# USB.net
KiCad netlist of a schematic drawn in Altium Designer
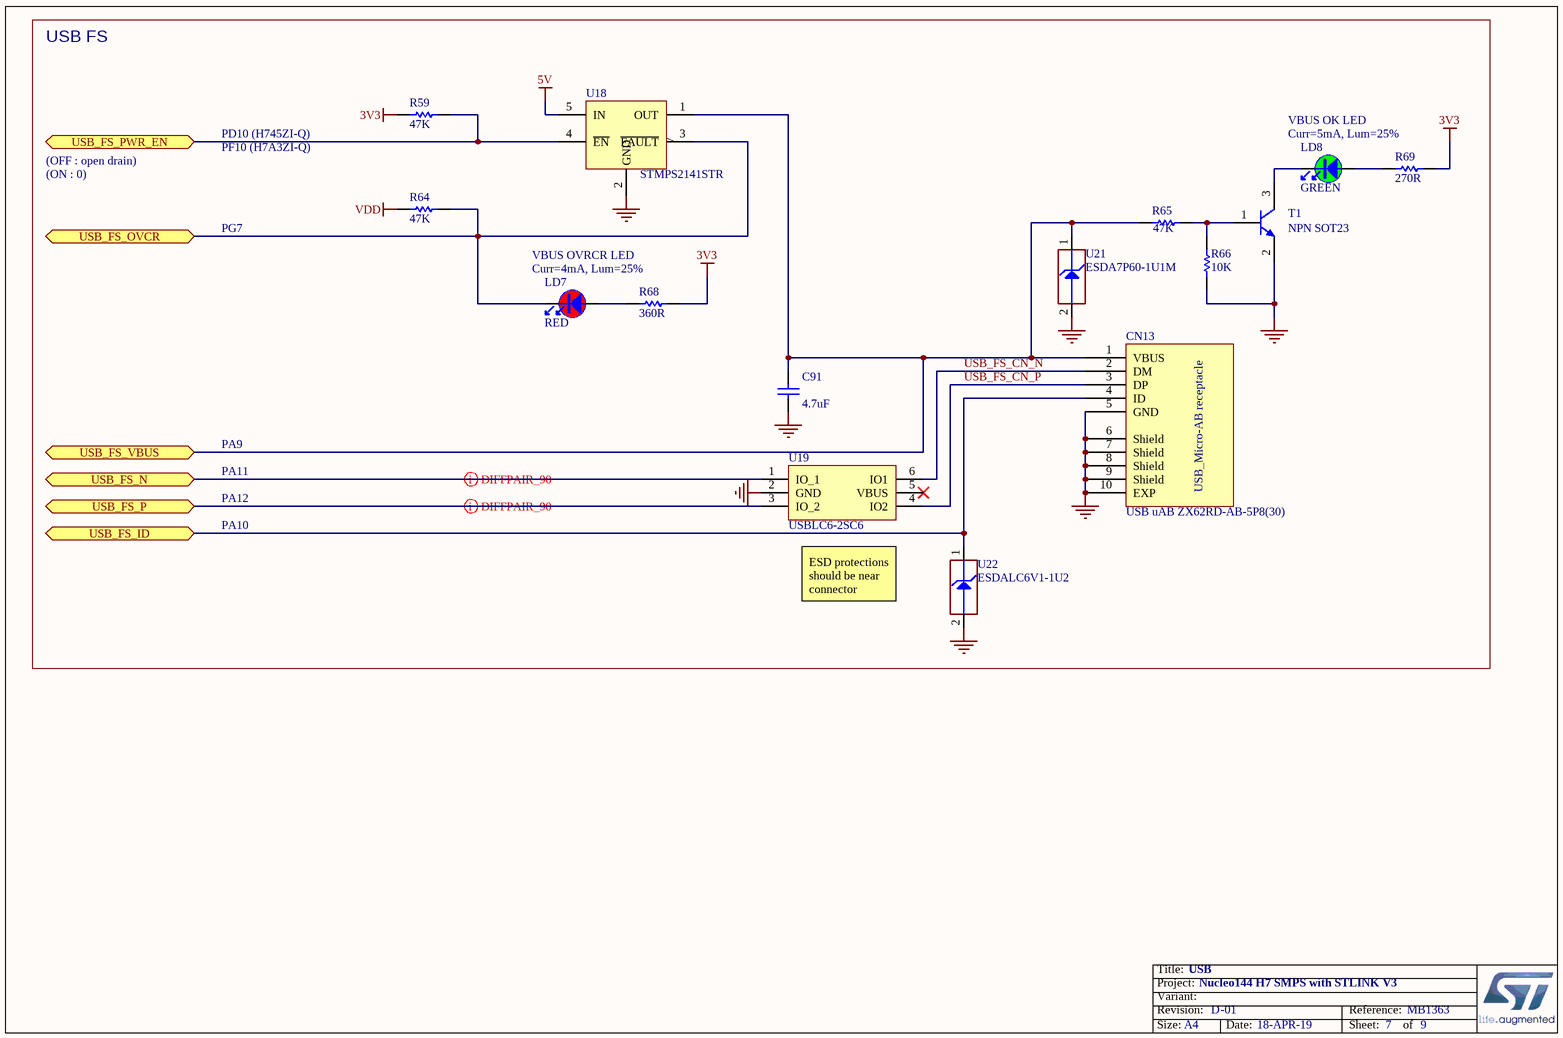
[diagram p0: USB.SchDoc]

(export (version "E")
  (design (tool "Eeschema 10.0.6"))
  (components
    (comp (ref "C91")
      (value "4.7uF")
      (footprint "C0603")
      (description "Capacitor, MLCC, 4.7uF, 16V, X5R, 10%, 0603, T=0.8mm")
      (fields
        (field (name "INTERNAL_PART_NUMBER") "MCD-00009")
        (field (name "MANUFACTURER_PART_NUMBER") "CC0603KRX5R7BB475")
        (field (name "PROVIDED_BY") "SUBCO")
      )
      (libsource (lib "MCD_PARTS_database") (part "Capacitor"))
    )
    (comp (ref "CN13")
      (value "USB uAB ZX62RD-AB-5P8(30)")
      (footprint "CON_USBMICROAB_MOLEX_47590-0001_H3")
      (fields
        (field (name "INTERNAL_PART_NUMBER") "MCD-00661")
        (field (name "MANUFACTURER_PART_NUMBER") "ZX62RD-AB-5P8(30)")
        (field (name "MANUFACTURER") "HIROSE")
        (field (name "PROVIDED_BY") "SUBCO")
      )
      (libsource (lib "MCD_PARTS_database") (part "USB_uAB_47590.0001"))
    )
    (comp (ref "LD7")
      (value "RED")
      (footprint "LED_0603_VISHAY_VLMS1300-GS08_RED_1A2K_H0P8")
      (description "LED Red, 0603 SMD, 2V Forward Voltage")
      (fields
        (field (name "INTERNAL_PART_NUMBER") "MCD-00587")
        (field (name "MANUFACTURER_PART_NUMBER") "VLMS1300-GS08")
        (field (name "PROVIDED_BY") "SUBCO")
      )
      (libsource (lib "MCD_PARTS_database") (part "LED_red"))
    )
    (comp (ref "LD8")
      (value "GREEN")
      (footprint "LED_0603_OSRAM_LG-Q396-PS-35_GREEN_1A2K_H0P4")
      (description "LED Green, 0603 SMD, Forward Voltage Typ=2V, Max=2.5V")
      (fields
        (field (name "INTERNAL_PART_NUMBER") "MCD-00588")
        (field (name "MANUFACTURER_PART_NUMBER") "LG Q396-PS-35")
        (field (name "PROVIDED_BY") "SUBCO")
      )
      (libsource (lib "MCD_PARTS_database") (part "LED_green"))
    )
    (comp (ref "R59")
      (value "47K")
      (footprint "R0402")
      (description "Resistor,47K,0402,1%,1/16W")
      (fields
        (field (name "INTERNAL_PART_NUMBER") "MCD-00063")
        (field (name "MANUFACTURER_PART_NUMBER") "RC0402FR-0747KL")
        (field (name "PROVIDED_BY") "SUBCO")
      )
      (libsource (lib "MCD_PARTS_database") (part "Resistor"))
    )
    (comp (ref "R64")
      (value "47K")
      (footprint "R0402")
      (description "Resistor,47K,0402,1%,1/16W")
      (fields
        (field (name "INTERNAL_PART_NUMBER") "MCD-00063")
        (field (name "MANUFACTURER_PART_NUMBER") "RC0402FR-0747KL")
        (field (name "PROVIDED_BY") "SUBCO")
      )
      (libsource (lib "MCD_PARTS_database") (part "Resistor"))
    )
    (comp (ref "R65")
      (value "47K")
      (footprint "R0402")
      (description "Resistor,47K,0402,1%,1/16W")
      (fields
        (field (name "INTERNAL_PART_NUMBER") "MCD-00063")
        (field (name "MANUFACTURER_PART_NUMBER") "RC0402FR-0747KL")
        (field (name "PROVIDED_BY") "SUBCO")
      )
      (libsource (lib "MCD_PARTS_database") (part "Resistor"))
    )
    (comp (ref "R66")
      (value "10K")
      (footprint "R0402")
      (description "Resistor,10K,0402,1%,1/16W")
      (fields
        (field (name "INTERNAL_PART_NUMBER") "MCD-00053")
        (field (name "MANUFACTURER_PART_NUMBER") "RC0402FR-0710KL")
        (field (name "PROVIDED_BY") "SUBCO")
      )
      (libsource (lib "MCD_PARTS_database") (part "Resistor"))
    )
    (comp (ref "R68")
      (value "360R")
      (footprint "R0402")
      (description "Resistor,360R,0402,1%,1/16W")
      (fields
        (field (name "INTERNAL_PART_NUMBER") "MCD-00461")
        (field (name "MANUFACTURER_PART_NUMBER") "RC0402FR-07360RL")
        (field (name "PROVIDED_BY") "SUBCO")
      )
      (libsource (lib "MCD_PARTS_database") (part "Resistor"))
    )
    (comp (ref "R69")
      (value "270R")
      (footprint "R0402")
      (description "Resistor,270R,0402,1%,1/16W")
      (fields
        (field (name "INTERNAL_PART_NUMBER") "MCD-00441")
        (field (name "MANUFACTURER_PART_NUMBER") "RC0402FR-07270RL")
        (field (name "PROVIDED_BY") "SUBCO")
      )
      (libsource (lib "MCD_PARTS_database") (part "Resistor"))
    )
    (comp (ref "T1")
      (value "NPN SOT23")
      (footprint "NPN_SOT23")
      (description "NPN Bipolar Transistor")
      (fields
        (field (name "INTERNAL_PART_NUMBER") "MCD-00073")
        (field (name "MANUFACTURER_PART_NUMBER") "BSR14")
        (field (name "PROVIDED_BY") "SUBCO")
      )
      (libsource (lib "MCD_PARTS_database") (part "9013-SOT23"))
    )
    (comp (ref "U18")
      (value "STMPS2141STR")
      (footprint "MOS_SOT23-5L")
      (description "Enhanced single channel power switches with active low enable pin")
      (fields
        (field (name "INTERNAL_PART_NUMBER") "MCD-00083")
        (field (name "MANUFACTURER") "STMICROELECTRONICS")
        (field (name "PROVIDED_BY") "SUBCO with ST control")
      )
      (libsource (lib "MCD_PARTS_database") (part "STMPS2141STR"))
    )
    (comp (ref "U19")
      (value "USBLC6-2SC6")
      (footprint "ESD_SOT23-6L")
      (description "Very low capacitance ESD protection")
      (fields
        (field (name "INTERNAL_PART_NUMBER") "MCD-00163")
        (field (name "MANUFACTURER") "STMICROELECTRONICS")
        (field (name "PROVIDED_BY") "SUBCO with ST control")
      )
      (libsource (lib "MCD_PARTS_database") (part "USBLC6-2SC6"))
    )
    (comp (ref "U21")
      (value "ESDA7P60-1U1M")
      (footprint "ESD_QFN2_1P6X1_P125")
      (description "High power transient voltage suppressor, 7V breakdown")
      (fields
        (field (name "INTERNAL_PART_NUMBER") "MCD-00251")
        (field (name "MANUFACTURER") "STMICROELECTRONICS")
        (field (name "PROVIDED_BY") "SUBCO with ST control")
      )
      (libsource (lib "MCD_PARTS_database") (part "ESD-TRANSIL"))
    )
    (comp (ref "U22")
      (value "ESDALC6V1-1U2")
      (footprint "ESD_ST0201")
      (description "ESD protection 6V1")
      (fields
        (field (name "INTERNAL_PART_NUMBER") "MCD-00170")
        (field (name "MANUFACTURER") "STMICROELECTRONICS")
        (field (name "PROVIDED_BY") "SUBCO with ST control")
      )
      (libsource (lib "MCD_PARTS_database") (part "ESD-TRANSIL"))
    )
  )
  (nets
    (net (code "1") (name "/USB_FS_CN_N") (class "Default")
      (node (ref "CN13") (pin "2") (pinfunction "DM_2") (pintype "passive"))
      (node (ref "U19") (pin "6") (pinfunction "IO1_6") (pintype "passive"))
    )
    (net (code "2") (name "/USB_FS_CN_P") (class "Default")
      (node (ref "CN13") (pin "3") (pinfunction "DP_3") (pintype "passive"))
      (node (ref "U19") (pin "4") (pinfunction "IO2_4") (pintype "passive"))
    )
    (net (code "3") (name "/USB_FS_ID") (class "Default")
      (node (ref "CN13") (pin "4") (pinfunction "ID_4") (pintype "passive"))
      (node (ref "U22") (pin "1") (pinfunction "IO1_1") (pintype "passive"))
    )
    (net (code "4") (name "/USB_FS_N") (class "Default")
      (node (ref "U19") (pin "1") (pinfunction "IO_1_1") (pintype "passive"))
    )
    (net (code "5") (name "/USB_FS_OVCR") (class "Default")
      (node (ref "LD7") (pin "2") (pintype "passive"))
      (node (ref "R64") (pin "1") (pinfunction "1_1") (pintype "passive"))
      (node (ref "U18") (pin "3") (pinfunction "~{FAULT}_3") (pintype "passive"))
    )
    (net (code "6") (name "/USB_FS_P") (class "Default")
      (node (ref "U19") (pin "3") (pinfunction "IO_2_3") (pintype "passive"))
    )
    (net (code "7") (name "/USB_FS_PWR_EN") (class "Default")
      (node (ref "R59") (pin "1") (pinfunction "1_1") (pintype "passive"))
      (node (ref "U18") (pin "4") (pinfunction "~{EN}_4") (pintype "passive"))
    )
    (net (code "8") (name "/USB_FS_VBUS") (class "Default")
      (node (ref "C91") (pin "2") (pinfunction "2_2") (pintype "passive"))
      (node (ref "CN13") (pin "1") (pinfunction "VBUS_1") (pintype "passive"))
      (node (ref "R65") (pin "1") (pinfunction "1_1") (pintype "passive"))
      (node (ref "U18") (pin "1") (pinfunction "OUT_1") (pintype "passive"))
      (node (ref "U21") (pin "1") (pinfunction "IO1_1") (pintype "passive"))
    )
    (net (code "9") (name "3V3") (class "Default")
      (node (ref "R59") (pin "2") (pinfunction "2_2") (pintype "passive"))
      (node (ref "R68") (pin "2") (pinfunction "2_2") (pintype "passive"))
      (node (ref "R69") (pin "2") (pinfunction "2_2") (pintype "passive"))
    )
    (net (code "10") (name "5V") (class "Default")
      (node (ref "U18") (pin "5") (pinfunction "IN_5") (pintype "passive"))
    )
    (net (code "11") (name "GND") (class "Default")
      (node (ref "C91") (pin "1") (pinfunction "1_1") (pintype "passive"))
      (node (ref "CN13") (pin "10") (pinfunction "EXP_10") (pintype "passive"))
      (node (ref "CN13") (pin "5") (pinfunction "GND_5") (pintype "passive"))
      (node (ref "CN13") (pin "6") (pinfunction "Shield_6") (pintype "passive"))
      (node (ref "CN13") (pin "7") (pinfunction "Shield_7") (pintype "passive"))
      (node (ref "CN13") (pin "8") (pinfunction "Shield_8") (pintype "passive"))
      (node (ref "CN13") (pin "9") (pinfunction "Shield_9") (pintype "passive"))
      (node (ref "R66") (pin "1") (pinfunction "1_1") (pintype "passive"))
      (node (ref "T1") (pin "2") (pinfunction "E_2") (pintype "passive"))
      (node (ref "U18") (pin "2") (pinfunction "GND_2") (pintype "passive"))
      (node (ref "U19") (pin "2") (pinfunction "GND_2") (pintype "passive"))
      (node (ref "U21") (pin "2") (pinfunction "GND_2") (pintype "passive"))
      (node (ref "U22") (pin "2") (pinfunction "GND_2") (pintype "passive"))
    )
    (net (code "12") (name "Net-(LD7-Pad1)") (class "Default")
      (node (ref "LD7") (pin "1") (pintype "passive"))
      (node (ref "R68") (pin "1") (pinfunction "1_1") (pintype "passive"))
    )
    (net (code "13") (name "Net-(LD8-Pad1)") (class "Default")
      (node (ref "LD8") (pin "1") (pintype "passive"))
      (node (ref "R69") (pin "1") (pinfunction "1_1") (pintype "passive"))
    )
    (net (code "14") (name "Net-(T1-B)") (class "Default")
      (node (ref "R65") (pin "2") (pinfunction "2_2") (pintype "passive"))
      (node (ref "R66") (pin "2") (pinfunction "2_2") (pintype "passive"))
      (node (ref "T1") (pin "1") (pinfunction "B_1") (pintype "passive"))
    )
    (net (code "15") (name "Net-(T1-C)") (class "Default")
      (node (ref "LD8") (pin "2") (pintype "passive"))
      (node (ref "T1") (pin "3") (pinfunction "C_3") (pintype "passive"))
    )
    (net (code "16") (name "VDD") (class "Default")
      (node (ref "R64") (pin "2") (pinfunction "2_2") (pintype "passive"))
    )
    (net (code "17") (name "unconnected-(U19-VBUS-Pad5)") (class "Default")
      (node (ref "U19") (pin "5") (pinfunction "VBUS_5") (pintype "passive+no_connect"))
    )
  )
)
